# BuckConverter_A_Connectors.net
KiCad netlist of a schematic drawn in Altium Designer
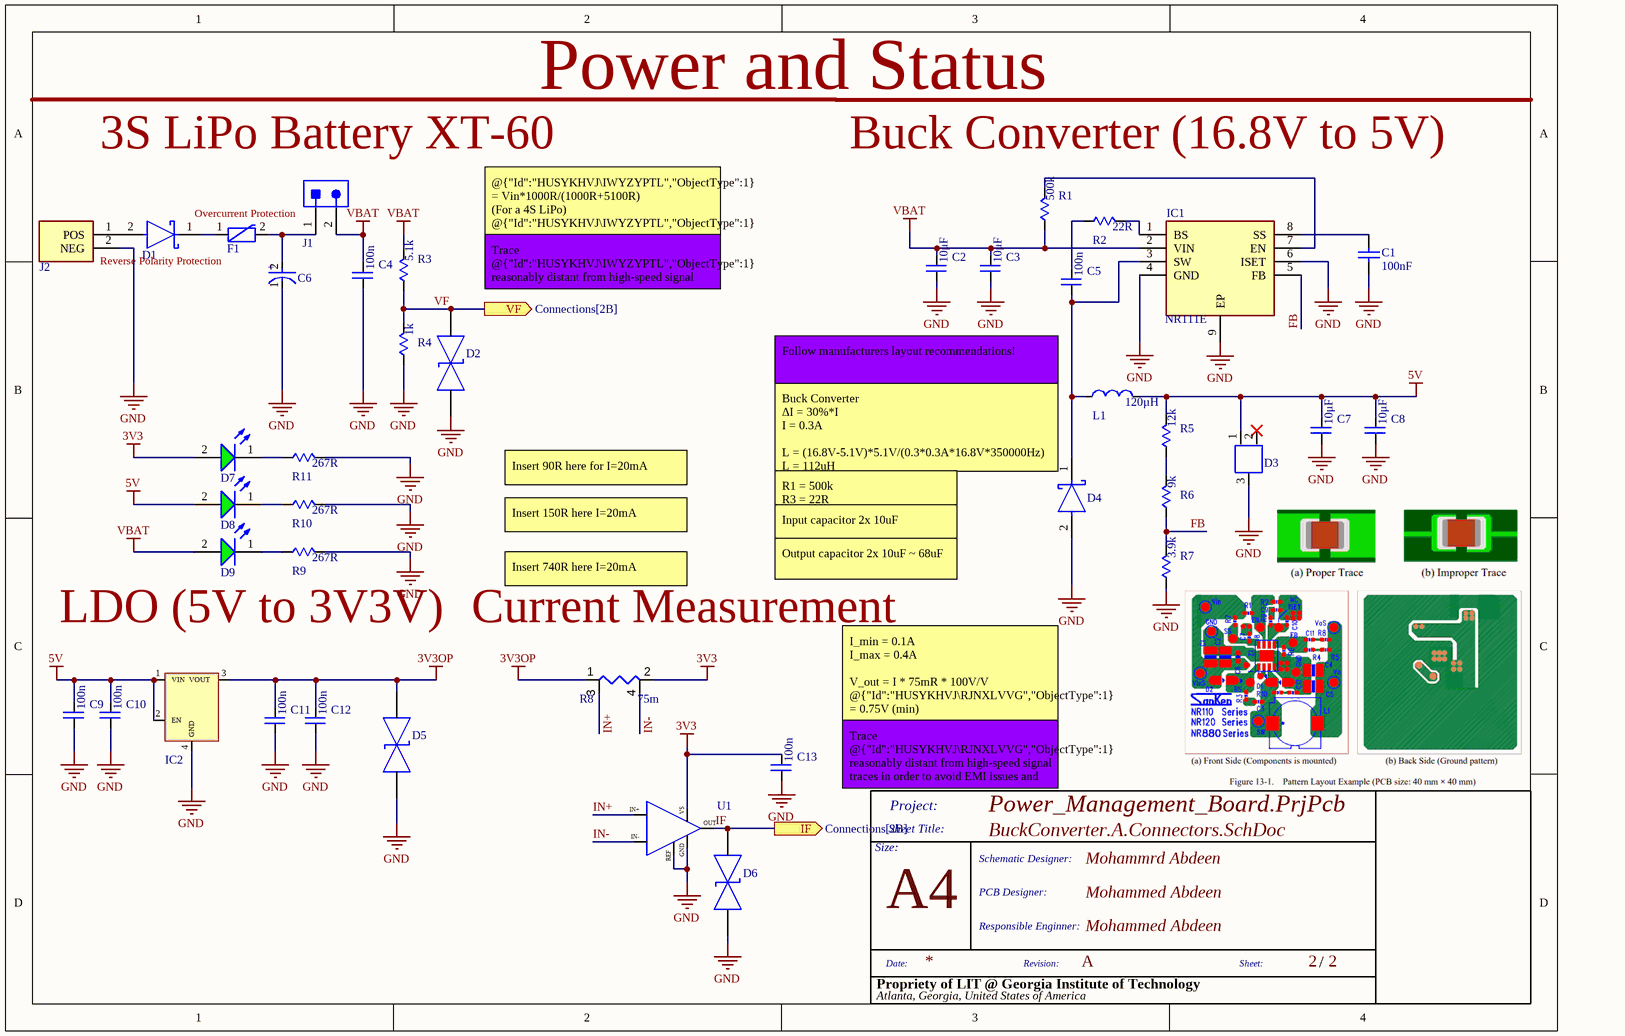
[diagram p0: BuckConverter.A.Connectors.SchDoc]

(export (version "E")
  (design (tool "Eeschema 10.0.6"))
  (components
    (comp (ref "C1")
      (value "100nF")
      (footprint "0603(1608)-CAP")
      (fields (field (name "TOLERANCE") "10%") (field (name "Comment") "GMK107B7104KAHT"))
      (libsource (lib "Georgia Tech GNC") (part "CAP-NONPOLAR"))
    )
    (comp (ref "C2")
      (value "GRM31CR71C106KAC7L")
      (footprint "1206-RES")
      (description "10 µF ±10% 16V Ceramic Capacitor X7R 1206 (3216 Metric)")
      (libsource (lib "USLI_Footprints") (part "CAP-1206-16V-10uF"))
    )
    (comp (ref "C3")
      (value "GRM31CR71C106KAC7L")
      (footprint "1206-RES")
      (description "10 µF ±10% 16V Ceramic Capacitor X7R 1206 (3216 Metric)")
      (libsource (lib "USLI_Footprints") (part "CAP-1206-16V-10uF"))
    )
    (comp (ref "C4")
      (value "KGM21NR71E104KT")
      (footprint "0805-RES")
      (description "0.1 µF ±10% 25V Ceramic Capacitor X7R 0805 (2012 Metric)")
      (libsource (lib "MySchLib") (part "CAP-0805-25V-100n"))
    )
    (comp (ref "C5")
      (value "KGM21NR71E104KT")
      (footprint "CAP-0805")
      (description "0.1 µF ±10% 25V Ceramic Capacitor X7R 0805 (2012 Metric)")
      (libsource (lib "USLI_Footprints") (part "CAP-0805-25V-100n"))
    )
    (comp (ref "C6")
      (value "EEE-FK1E470P")
      (footprint "FP-FKD-MFG")
      (description "47 µF 25 V Aluminum Electrolytic Capacitors Radial, Can - SMD 2000 Hrs @ 105°C")
      (fields (field (name "MANUFACTURER") "Panasonic Electronic Components"))
      (libsource (lib "MySchLib") (part "CAP-RADIALSMD-25V(BIAS)"))
    )
    (comp (ref "C7")
      (value "GRM31CR71C106KAC7L")
      (footprint "1206-RES")
      (description "10 µF ±10% 16V Ceramic Capacitor X7R 1206 (3216 Metric)")
      (libsource (lib "USLI_Footprints") (part "CAP-1206-16V-10uF"))
    )
    (comp (ref "C8")
      (value "GRM31CR71C106KAC7L")
      (footprint "1206-RES")
      (description "10 µF ±10% 16V Ceramic Capacitor X7R 1206 (3216 Metric)")
      (libsource (lib "USLI_Footprints") (part "CAP-1206-16V-10uF"))
    )
    (comp (ref "C9")
      (value "KGM21NR71E104KT")
      (footprint "0805-RES")
      (description "0.1 µF ±10% 25V Ceramic Capacitor X7R 0805 (2012 Metric)")
      (libsource (lib "MySchLib") (part "CAP-0805-25V-100n"))
    )
    (comp (ref "C10")
      (value "KGM21NR71E104KT")
      (footprint "0805-RES")
      (description "0.1 µF ±10% 25V Ceramic Capacitor X7R 0805 (2012 Metric)")
      (libsource (lib "MySchLib") (part "CAP-0805-25V-100n"))
    )
    (comp (ref "C11")
      (value "KGM21NR71E104KT")
      (footprint "0805-RES")
      (description "0.1 µF ±10% 25V Ceramic Capacitor X7R 0805 (2012 Metric)")
      (libsource (lib "MySchLib") (part "CAP-0805-25V-100n"))
    )
    (comp (ref "C12")
      (value "KGM21NR71E104KT")
      (footprint "0805-RES")
      (description "0.1 µF ±10% 25V Ceramic Capacitor X7R 0805 (2012 Metric)")
      (libsource (lib "MySchLib") (part "CAP-0805-25V-100n"))
    )
    (comp (ref "C13")
      (value "KGM21NR71E104KT")
      (footprint "0805-RES")
      (description "0.1 µF ±10% 25V Ceramic Capacitor X7R 0805 (2012 Metric)")
      (libsource (lib "MySchLib") (part "CAP-0805-25V-100n"))
    )
    (comp (ref "D1")
      (value "APT60S20BG")
      (footprint "APT60S20BG")
      (description "Diode 200 V 75A Through Hole TO-247 [B]")
      (libsource (lib "MySchLib") (part "SCHOTTKY-TH-200V-75A"))
    )
    (comp (ref "D2")
      (value "PESD3V3Y1BSFYL")
      (footprint "FP-SOD962-2-CA-MFG")
      (description "3.7V (Typ) Clamp Ipp Tvs Diode Surface Mount DSN0603-2")
      (libsource (lib "MySchLib") (part "TVS-3V3-4V2"))
    )
    (comp (ref "D3")
      (value "824021")
      (footprint "824021")
      (description "7V Clamp 15A (8/20µs) Ipp Tvs Diode Surface Mount SOT-23-3")
      (libsource (lib "USLI_Footprints") (part "TVS-6.1V-7V"))
    )
    (comp (ref "D4")
      (value "NSR20F40NXT5G")
      (footprint "0603-SchottkyDIODE")
      (description "Diode 40 V 2A Surface Mount 2-DSN (1.6x0.8), (0603)")
      (fields (field (name "MANUFACTURER") "onsemi"))
      (libsource (lib "USLI_Footprints") (part "SCHOTTKY-0603-40V-2A"))
    )
    (comp (ref "D5")
      (value "PESD3V3Y1BSFYL")
      (footprint "FP-SOD962-2-CA-MFG")
      (description "3.7V (Typ) Clamp Ipp Tvs Diode Surface Mount DSN0603-2")
      (libsource (lib "MySchLib") (part "TVS-3V3-4V2"))
    )
    (comp (ref "D6")
      (value "PESD3V3Y1BSFYL")
      (footprint "FP-SOD962-2-CA-MFG")
      (description "3.7V (Typ) Clamp Ipp Tvs Diode Surface Mount DSN0603-2")
      (libsource (lib "MySchLib") (part "TVS-3V3-4V2"))
    )
    (comp (ref "D7")
      (value "LTST-C190KGKT")
      (footprint "FP-LTST-C190KGKT-MFG")
      (description "Green 571nm LED Indication - Discrete 2V 0603 (1608 Metric)")
      (libsource (lib "MainMCUSch") (part "LED-0603-Green_"))
    )
    (comp (ref "D8")
      (value "LTST-C190KGKT")
      (footprint "FP-LTST-C190KGKT-MFG")
      (description "Green 571nm LED Indication - Discrete 2V 0603 (1608 Metric)")
      (libsource (lib "MainMCUSch") (part "LED-0603-Green_"))
    )
    (comp (ref "D9")
      (value "LTST-C190KGKT")
      (footprint "FP-LTST-C190KGKT-MFG")
      (description "Green 571nm LED Indication - Discrete 2V 0603 (1608 Metric)")
      (libsource (lib "MainMCUSch") (part "LED-0603-Green_"))
    )
    (comp (ref "F1")
      (value "MF-USHT050KX-2")
      (footprint "1210-IND")
      (description "Polymeric PTC Resettable Fuse 30V 500 mA Ih Surface Mount 1210 (3225 Metric), Concave")
      (libsource (lib "USLI_Footprints") (part "DC-FUSE-2.5A"))
    )
    (comp (ref "IC1")
      (value "NR111E")
      (footprint "SOIC-8-Thermally-Enhanced")
      (description "Integrated Circuit")
      (libsource (lib "Georgia Tech GNC") (part "NR111E"))
    )
    (comp (ref "IC2")
      (value "AP2114HA-3.3TRG1")
      (footprint "TO-261AA")
      (description "Linear Voltage Regulator IC Positive Fixed 1 Output 1A SOT-223-3")
      (fields (field (name "MANUFACTURER") "Diodes Incorporated"))
      (libsource (lib "USLI_Footprints") (part "LDO-6V-3V3"))
    )
    (comp (ref "J1")
      (value "61300211121")
      (footprint "HEADER-2-Pin")
      (description "Connector Header Through Hole 2 position 0.100\" (2.54mm)")
      (fields (field (name "MANUFACTURER") "Würth Elektronik"))
      (libsource (lib "MySchLib") (part "Header-2-Pin-Male"))
    )
    (comp (ref "J2")
      (value "PRT-10474")
      (footprint "AMASS_XT60PW-M")
      (description "XT60 CONNECTORS FEMALE PAIR")
      (libsource (lib "MySchLib") (part "XT60-F"))
    )
    (comp (ref "L1")
      (value "SRR1210-121M")
      (footprint "SRR1210-121M")
      (description "120 µH Shielded Drum Core, Wirewound Inductor 2.3 A 170mOhm Max Nonstandard")
      (libsource (lib "USLI_Footprints") (part "IND-120uH-2.3A"))
    )
    (comp (ref "R1")
      (value "RNCF0805BTE500K")
      (footprint "0805-RES")
      (description "500 kOhms ±0.1% 0.125W, 1/8W Chip Resistor 0805 (2012 Metric) Automotive AEC-Q200 Thin Film")
      (libsource (lib "USLI_Footprints") (part "RES-0805-500k"))
    )
    (comp (ref "R2")
      (value "RC0805FR-0722RL")
      (footprint "0805-RES")
      (description "22 Ohms ±1% 0.125W, 1/8W Chip Resistor 0805 (2012 Metric) Moisture Resistant Thick Film")
      (libsource (lib "USLI_Footprints") (part "RES-0805-22R"))
    )
    (comp (ref "R3")
      (value "RC0603FR-075K1L")
      (footprint "0603-RES")
      (description "5.1 kOhms ±1% 0.1W, 1/10W Chip Resistor 0603 (1608 Metric) Moisture Resistant Thick Film")
      (fields (field (name "MANUFACTURER") "YAGEO"))
      (libsource (lib "USLI_Footprints") (part "RES-0603-5.1k"))
    )
    (comp (ref "R4")
      (value "ESR03EZPF1001")
      (footprint "0603-RES")
      (libsource (lib "MySchLib") (part "RES-0603-1k_"))
    )
    (comp (ref "R5")
      (value "RMCF0805JT12K0")
      (footprint "0805-RES")
      (description "12 kOhms ±5% 0.125W, 1/8W Chip Resistor 0805 (2012 Metric) Automotive AEC-Q200 Thick Film")
      (libsource (lib "USLI_Footprints") (part "RES-0805-12k"))
    )
    (comp (ref "R6")
      (value "RT0805BRE079KL")
      (footprint "0805-RES")
      (description "9 kOhms ±0.1% 0.125W, 1/8W Chip Resistor 0805 (2012 Metric) Thin Film")
      (libsource (lib "USLI_Footprints") (part "RES-0805-9k"))
    )
    (comp (ref "R7")
      (value "CRG0805F3K9")
      (footprint "0805-RES")
      (description "3.9 kOhms ±1% 0.125W, 1/8W Chip Resistor 0805 (2012 Metric) Thick Film")
      (libsource (lib "USLI_Footprints") (part "RES-0805-3.9k"))
    )
    (comp (ref "R8")
      (value "LVK12R075DER")
      (footprint "LVK12R075DER")
      (libsource (lib "MySchLib") (part "RES-1206-75m-KELVIN"))
    )
    (comp (ref "R9")
      (value "ERJ-3EKF2670V")
      (footprint "0603-RES")
      (description "267 Ohms ±1% 0.1W, 1/10W Chip Resistor 0603 (1608 Metric) Automotive AEC-Q200 Thick Film")
      (fields (field (name "MANUFACTURER") "Panasonic Electronic Components"))
      (libsource (lib "MainMCUSch") (part "RES-0603-267R"))
    )
    (comp (ref "R10")
      (value "ERJ-3EKF2670V")
      (footprint "0603-RES")
      (description "267 Ohms ±1% 0.1W, 1/10W Chip Resistor 0603 (1608 Metric) Automotive AEC-Q200 Thick Film")
      (fields (field (name "MANUFACTURER") "Panasonic Electronic Components"))
      (libsource (lib "MainMCUSch") (part "RES-0603-267R"))
    )
    (comp (ref "R11")
      (value "ERJ-3EKF2670V")
      (footprint "0603-RES")
      (description "267 Ohms ±1% 0.1W, 1/10W Chip Resistor 0603 (1608 Metric) Automotive AEC-Q200 Thick Film")
      (fields (field (name "MANUFACTURER") "Panasonic Electronic Components"))
      (libsource (lib "MainMCUSch") (part "RES-0603-267R"))
    )
    (comp (ref "U1")
      (value "INA181A3IDBVR")
      (footprint "SOT95P280X145-6N")
      (description "Current Sense Amplifier 1 Circuit Rail-to-Rail SOT-23-6")
      (fields (field (name "MANUFACTURER") "Texas Instruments"))
      (libsource (lib "MySchLib") (part "AMP-100V/V-SOT23-6"))
    )
  )
  (nets
    (net (code "1") (name "/FB") (class "Default")
      (node (ref "IC1") (pin "5") (pinfunction "FB_5") (pintype "passive"))
      (node (ref "R6") (pin "1") (pintype "passive"))
      (node (ref "R7") (pin "2") (pintype "passive"))
    )
    (net (code "2") (name "/IF") (class "Default")
      (node (ref "D6") (pin "2") (pintype "passive"))
      (node (ref "U1") (pin "OUT") (pintype "passive"))
    )
    (net (code "3") (name "/IN+") (class "Default")
      (node (ref "R8") (pin "3") (pinfunction "E1_3") (pintype "passive"))
      (node (ref "U1") (pin "IN+") (pintype "passive"))
    )
    (net (code "4") (name "/IN-") (class "Default")
      (node (ref "R8") (pin "4") (pinfunction "E2_4") (pintype "passive"))
      (node (ref "U1") (pin "IN-") (pintype "passive"))
    )
    (net (code "5") (name "/VF") (class "Default")
      (node (ref "D2") (pin "2") (pintype "passive"))
      (node (ref "R3") (pin "1") (pintype "passive"))
      (node (ref "R4") (pin "2") (pintype "passive"))
    )
    (net (code "6") (name "3V3") (class "Default")
      (node (ref "C13") (pin "2") (pintype "passive"))
      (node (ref "D7") (pin "2") (pinfunction "A_2") (pintype "passive"))
      (node (ref "R8") (pin "2") (pinfunction "I2_2") (pintype "passive"))
      (node (ref "U1") (pin "VS") (pintype "passive"))
    )
    (net (code "7") (name "3V3OP") (class "Default")
      (node (ref "C11") (pin "2") (pintype "passive"))
      (node (ref "C12") (pin "2") (pintype "passive"))
      (node (ref "D5") (pin "2") (pintype "passive"))
      (node (ref "IC2") (pin "3") (pinfunction "VOUT_3") (pintype "passive"))
      (node (ref "R8") (pin "1") (pinfunction "I1_1") (pintype "passive"))
    )
    (net (code "8") (name "5V") (class "Default")
      (node (ref "C10") (pin "2") (pintype "passive"))
      (node (ref "C7") (pin "2") (pintype "passive"))
      (node (ref "C8") (pin "2") (pintype "passive"))
      (node (ref "C9") (pin "2") (pintype "passive"))
      (node (ref "D3") (pin "1") (pintype "passive"))
      (node (ref "D8") (pin "2") (pinfunction "A_2") (pintype "passive"))
      (node (ref "IC2") (pin "1") (pinfunction "VIN_1") (pintype "passive"))
      (node (ref "IC2") (pin "2") (pinfunction "EN_2") (pintype "passive"))
      (node (ref "L1") (pin "2") (pintype "power_in"))
      (node (ref "R5") (pin "2") (pintype "passive"))
    )
    (net (code "9") (name "GND") (class "Default")
      (node (ref "C1") (pin "1") (pinfunction "1_1") (pintype "passive"))
      (node (ref "C10") (pin "1") (pintype "passive"))
      (node (ref "C11") (pin "1") (pintype "passive"))
      (node (ref "C12") (pin "1") (pintype "passive"))
      (node (ref "C13") (pin "1") (pintype "passive"))
      (node (ref "C2") (pin "1") (pintype "passive"))
      (node (ref "C3") (pin "1") (pintype "passive"))
      (node (ref "C4") (pin "1") (pintype "passive"))
      (node (ref "C6") (pin "1") (pinfunction "C_1") (pintype "passive"))
      (node (ref "C7") (pin "1") (pintype "passive"))
      (node (ref "C8") (pin "1") (pintype "passive"))
      (node (ref "C9") (pin "1") (pintype "passive"))
      (node (ref "D2") (pin "1") (pintype "passive"))
      (node (ref "D3") (pin "3") (pintype "passive"))
      (node (ref "D4") (pin "2") (pinfunction "A_2") (pintype "passive"))
      (node (ref "D5") (pin "1") (pintype "passive"))
      (node (ref "D6") (pin "1") (pintype "passive"))
      (node (ref "IC1") (pin "4") (pinfunction "GND_4") (pintype "passive"))
      (node (ref "IC1") (pin "6") (pinfunction "ISET_6") (pintype "passive"))
      (node (ref "IC1") (pin "9") (pinfunction "EP_9") (pintype "passive"))
      (node (ref "IC2") (pin "4") (pinfunction "GND_4") (pintype "passive"))
      (node (ref "J2") (pin "2") (pinfunction "NEG_2") (pintype "passive"))
      (node (ref "R10") (pin "2") (pintype "passive"))
      (node (ref "R11") (pin "2") (pintype "passive"))
      (node (ref "R4") (pin "1") (pintype "passive"))
      (node (ref "R7") (pin "1") (pintype "passive"))
      (node (ref "R9") (pin "2") (pintype "passive"))
      (node (ref "U1") (pin "GND") (pintype "passive"))
      (node (ref "U1") (pin "REF") (pintype "passive"))
    )
    (net (code "10") (name "Net-(C5-Pad2)") (class "Default")
      (node (ref "C5") (pin "2") (pintype "passive"))
      (node (ref "R2") (pin "1") (pintype "passive"))
    )
    (net (code "11") (name "Net-(C6-A)") (class "Default")
      (node (ref "C6") (pin "2") (pinfunction "A_2") (pintype "passive"))
      (node (ref "F1") (pin "2") (pinfunction "2_2") (pintype "passive"))
      (node (ref "J1") (pin "1") (pinfunction "1_1") (pintype "passive"))
    )
    (net (code "12") (name "Net-(D1-A)") (class "Default")
      (node (ref "D1") (pin "2") (pinfunction "A_2") (pintype "passive"))
      (node (ref "J2") (pin "1") (pinfunction "POS_1") (pintype "passive"))
    )
    (net (code "13") (name "Net-(D1-C)") (class "Default")
      (node (ref "D1") (pin "1") (pinfunction "C_1") (pintype "passive"))
      (node (ref "F1") (pin "1") (pinfunction "2_1") (pintype "passive"))
    )
    (net (code "14") (name "Net-(D4-C)") (class "Default")
      (node (ref "C5") (pin "1") (pintype "passive"))
      (node (ref "D4") (pin "1") (pinfunction "C_1") (pintype "passive"))
      (node (ref "IC1") (pin "3") (pinfunction "SW_3") (pintype "passive"))
      (node (ref "L1") (pin "1") (pintype "power_in"))
    )
    (net (code "15") (name "Net-(D7-K)") (class "Default")
      (node (ref "D7") (pin "1") (pinfunction "K_1") (pintype "passive"))
      (node (ref "R11") (pin "1") (pintype "passive"))
    )
    (net (code "16") (name "Net-(D8-K)") (class "Default")
      (node (ref "D8") (pin "1") (pinfunction "K_1") (pintype "passive"))
      (node (ref "R10") (pin "1") (pintype "passive"))
    )
    (net (code "17") (name "Net-(D9-K)") (class "Default")
      (node (ref "D9") (pin "1") (pinfunction "K_1") (pintype "passive"))
      (node (ref "R9") (pin "1") (pintype "passive"))
    )
    (net (code "18") (name "Net-(IC1-BS)") (class "Default")
      (node (ref "IC1") (pin "1") (pinfunction "BS_1") (pintype "passive"))
      (node (ref "R2") (pin "2") (pintype "passive"))
    )
    (net (code "19") (name "Net-(IC1-EN)") (class "Default")
      (node (ref "IC1") (pin "7") (pinfunction "EN_7") (pintype "passive"))
      (node (ref "R1") (pin "2") (pintype "passive"))
    )
    (net (code "20") (name "Net-(IC1-SS)") (class "Default")
      (node (ref "C1") (pin "2") (pinfunction "2_2") (pintype "passive"))
      (node (ref "IC1") (pin "8") (pinfunction "SS_8") (pintype "passive"))
    )
    (net (code "21") (name "Net-(R5-Pad1)") (class "Default")
      (node (ref "R5") (pin "1") (pintype "passive"))
      (node (ref "R6") (pin "2") (pintype "passive"))
    )
    (net (code "22") (name "VBAT") (class "Default")
      (node (ref "C2") (pin "2") (pintype "passive"))
      (node (ref "C3") (pin "2") (pintype "passive"))
      (node (ref "C4") (pin "2") (pintype "passive"))
      (node (ref "D9") (pin "2") (pinfunction "A_2") (pintype "passive"))
      (node (ref "IC1") (pin "2") (pinfunction "VIN_2") (pintype "passive"))
      (node (ref "J1") (pin "2") (pinfunction "2_2") (pintype "passive"))
      (node (ref "R1") (pin "1") (pintype "passive"))
      (node (ref "R3") (pin "2") (pintype "passive"))
    )
    (net (code "23") (name "unconnected-(D3-Pad2)") (class "Default")
      (node (ref "D3") (pin "2") (pintype "passive+no_connect"))
    )
  )
)
